# V4-AddOnESP8266-V01-001.net
KiCad netlist of a schematic drawn in EAGLE
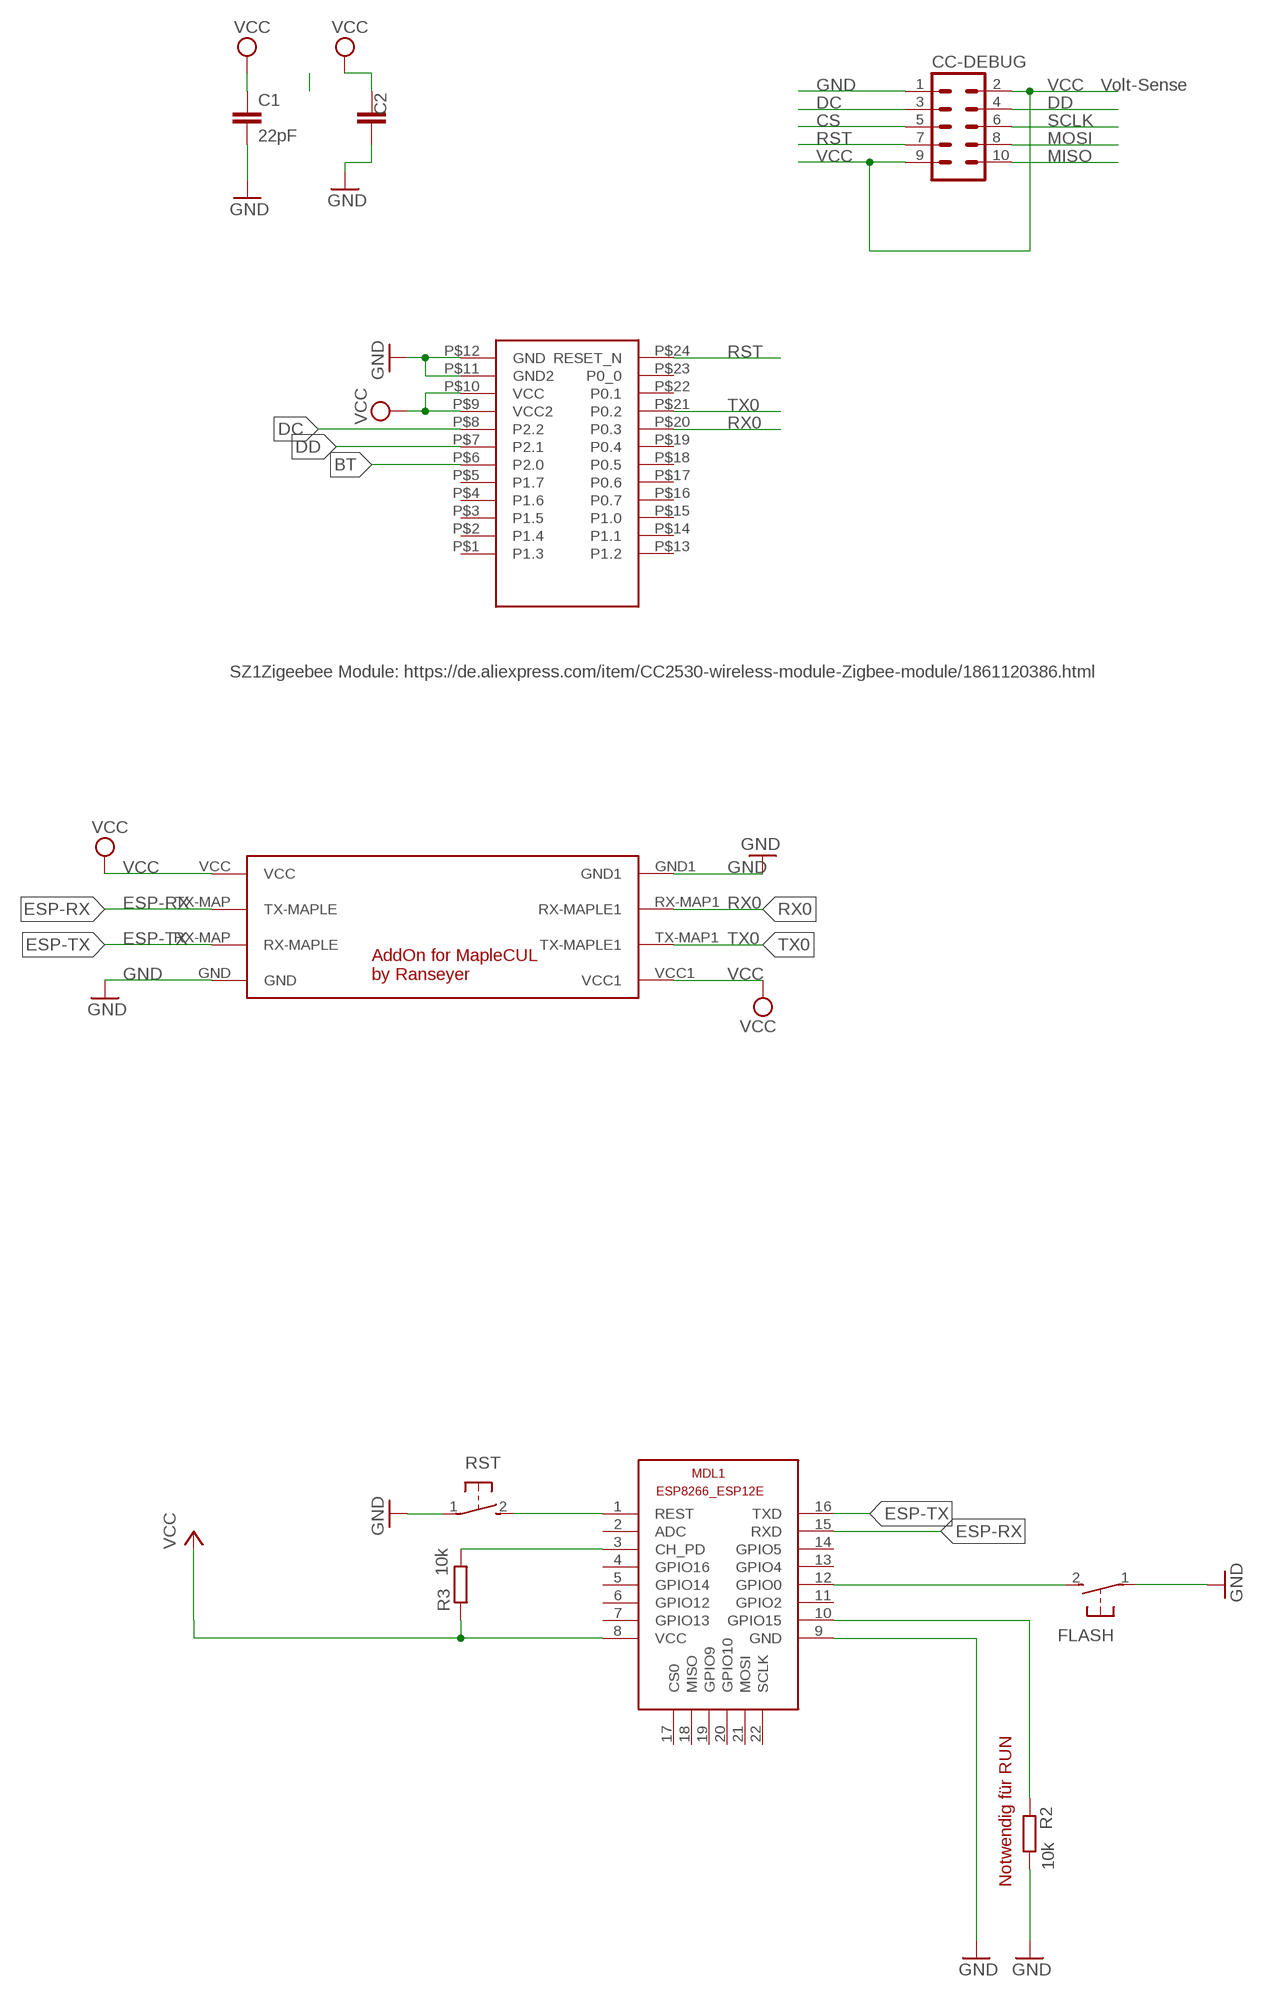
[diagram p0: schematic, sheet 1]

(export (version "E")
  (design (tool "Eeschema 10.0.6"))
  (components
    (comp (ref "C1")
      (value "22pF")
      (footprint "eagle-import:C0805")
      (libsource (lib "eagle-import") (part "C-EUC0805"))
    )
    (comp (ref "C2")
      (value "C-EUC1812")
      (footprint "eagle-import:C1812")
      (libsource (lib "eagle-import") (part "C-EUC1812"))
    )
    (comp (ref "CC-DEBUG")
      (value "CONN_05X2SHD_LOCK")
      (footprint "eagle-import:2X5-SHROUDED_LOCK")
      (libsource (lib "eagle-import") (part "CONN_05X2SHD_LOCK"))
    )
    (comp (ref "FLASH")
      (value "DTSM-3")
      (footprint "eagle-import:DTSM-3")
      (libsource (lib "eagle-import") (part "DTSM-3"))
    )
    (comp (ref "MDL1")
      (value "ESP8266-12EESP8266-ESP12E")
      (footprint "eagle-import:ESP8266-ESP12E")
      (libsource (lib "eagle-import") (part "ESP8266-12EESP8266-ESP12E"))
    )
    (comp (ref "R2")
      (value "10k")
      (footprint "eagle-import:M1206")
      (libsource (lib "eagle-import") (part "R-EU_M1206"))
    )
    (comp (ref "R3")
      (value "10k")
      (footprint "eagle-import:M1206")
      (libsource (lib "eagle-import") (part "R-EU_M1206"))
    )
    (comp (ref "RST")
      (value "DTSM-3")
      (footprint "eagle-import:DTSM-3")
      (libsource (lib "eagle-import") (part "DTSM-3"))
    )
    (comp (ref "U$1")
      (value "MAPLE-CUL-ADDON-V01")
      (footprint "eagle-import:MAPLE-CUL-V01")
      (libsource (lib "eagle-import") (part "MAPLE-CUL-ADDON-V01"))
    )
    (comp (ref "U$2")
      (value "CC2530")
      (footprint "eagle-import:SZ1ZIGBEE-SMD")
      (libsource (lib "eagle-import") (part "CC2530"))
    )
  )
  (nets
    (net (code "1") (name "/CS") (class "Default")
      (node (ref "CC-DEBUG") (pin "5") (pinfunction "5_5") (pintype "passive"))
    )
    (net (code "2") (name "/MISO") (class "Default")
      (node (ref "CC-DEBUG") (pin "10") (pinfunction "10_10") (pintype "passive"))
    )
    (net (code "3") (name "/MOSI") (class "Default")
      (node (ref "CC-DEBUG") (pin "8") (pinfunction "8_8") (pintype "passive"))
    )
    (net (code "4") (name "/RST") (class "Default")
      (node (ref "CC-DEBUG") (pin "7") (pinfunction "7_7") (pintype "passive"))
      (node (ref "U$2") (pin "P$24") (pinfunction "RESET_N_P$24") (pintype "bidirectional"))
    )
    (net (code "5") (name "/SCLK") (class "Default")
      (node (ref "CC-DEBUG") (pin "6") (pinfunction "6_6") (pintype "passive"))
    )
    (net (code "6") (name "BT") (class "Default")
      (node (ref "U$2") (pin "P$6") (pinfunction "P2.0_P$6") (pintype "bidirectional"))
    )
    (net (code "7") (name "DC") (class "Default")
      (node (ref "CC-DEBUG") (pin "3") (pinfunction "3_3") (pintype "passive"))
      (node (ref "U$2") (pin "P$8") (pinfunction "P2.2_P$8") (pintype "bidirectional"))
    )
    (net (code "8") (name "DD") (class "Default")
      (node (ref "CC-DEBUG") (pin "4") (pinfunction "4_4") (pintype "passive"))
      (node (ref "U$2") (pin "P$7") (pinfunction "P2.1_P$7") (pintype "bidirectional"))
    )
    (net (code "9") (name "ESP-RX") (class "Default")
      (node (ref "MDL1") (pin "15") (pinfunction "RXD_15") (pintype "bidirectional"))
      (node (ref "U$1") (pin "TX-MAP") (pinfunction "TX-MAPLE_TX-MAP") (pintype "bidirectional"))
    )
    (net (code "10") (name "ESP-TX") (class "Default")
      (node (ref "MDL1") (pin "16") (pinfunction "TXD_16") (pintype "bidirectional"))
      (node (ref "U$1") (pin "RX-MAP") (pinfunction "RX-MAPLE_RX-MAP") (pintype "bidirectional"))
    )
    (net (code "11") (name "GND") (class "Default")
      (node (ref "C1") (pin "2") (pinfunction "2_2") (pintype "passive"))
      (node (ref "C2") (pin "1") (pinfunction "1_1") (pintype "passive"))
      (node (ref "CC-DEBUG") (pin "1") (pinfunction "1_1") (pintype "passive"))
      (node (ref "FLASH") (pin "1") (pinfunction "1_1") (pintype "passive"))
      (node (ref "MDL1") (pin "9") (pinfunction "GND_9") (pintype "bidirectional"))
      (node (ref "R2") (pin "2") (pinfunction "2_2") (pintype "passive"))
      (node (ref "RST") (pin "1") (pinfunction "1_1") (pintype "passive"))
      (node (ref "U$1") (pin "GND") (pinfunction "GND_GND") (pintype "bidirectional"))
      (node (ref "U$1") (pin "GND1") (pinfunction "GND1_GND1") (pintype "bidirectional"))
      (node (ref "U$2") (pin "P$11") (pinfunction "GND2_P$11") (pintype "bidirectional"))
      (node (ref "U$2") (pin "P$12") (pinfunction "GND_P$12") (pintype "bidirectional"))
    )
    (net (code "12") (name "Net-(MDL1-CH_PD)") (class "Default")
      (node (ref "MDL1") (pin "3") (pinfunction "CH_PD_3") (pintype "bidirectional"))
      (node (ref "R3") (pin "2") (pinfunction "2_2") (pintype "passive"))
    )
    (net (code "13") (name "Net-(MDL1-GPIO0)") (class "Default")
      (node (ref "FLASH") (pin "2") (pinfunction "2_2") (pintype "passive"))
      (node (ref "MDL1") (pin "12") (pinfunction "GPIO0_12") (pintype "bidirectional"))
    )
    (net (code "14") (name "Net-(MDL1-GPIO15)") (class "Default")
      (node (ref "MDL1") (pin "10") (pinfunction "GPIO15_10") (pintype "bidirectional"))
      (node (ref "R2") (pin "1") (pinfunction "1_1") (pintype "passive"))
    )
    (net (code "15") (name "Net-(MDL1-REST)") (class "Default")
      (node (ref "MDL1") (pin "1") (pinfunction "REST_1") (pintype "bidirectional"))
      (node (ref "RST") (pin "2") (pinfunction "2_2") (pintype "passive"))
    )
    (net (code "16") (name "RX0") (class "Default")
      (node (ref "U$1") (pin "RX-MAP1") (pinfunction "RX-MAPLE1_RX-MAP1") (pintype "bidirectional"))
      (node (ref "U$2") (pin "P$20") (pinfunction "P0.3_P$20") (pintype "bidirectional"))
    )
    (net (code "17") (name "TX0") (class "Default")
      (node (ref "U$1") (pin "TX-MAP1") (pinfunction "TX-MAPLE1_TX-MAP1") (pintype "bidirectional"))
      (node (ref "U$2") (pin "P$21") (pinfunction "P0.2_P$21") (pintype "bidirectional"))
    )
    (net (code "18") (name "VCC") (class "Default")
      (node (ref "C1") (pin "1") (pinfunction "1_1") (pintype "passive"))
      (node (ref "C2") (pin "2") (pinfunction "2_2") (pintype "passive"))
      (node (ref "CC-DEBUG") (pin "2") (pinfunction "2_2") (pintype "passive"))
      (node (ref "CC-DEBUG") (pin "9") (pinfunction "9_9") (pintype "passive"))
      (node (ref "MDL1") (pin "8") (pinfunction "VCC_8") (pintype "bidirectional"))
      (node (ref "R3") (pin "1") (pinfunction "1_1") (pintype "passive"))
      (node (ref "U$1") (pin "VCC") (pinfunction "VCC_VCC") (pintype "bidirectional"))
      (node (ref "U$1") (pin "VCC1") (pinfunction "VCC1_VCC1") (pintype "bidirectional"))
      (node (ref "U$2") (pin "P$10") (pinfunction "VCC_P$10") (pintype "bidirectional"))
      (node (ref "U$2") (pin "P$9") (pinfunction "VCC2_P$9") (pintype "bidirectional"))
    )
    (net (code "19") (name "unconnected-(MDL1-ADC-Pad2)") (class "Default")
      (node (ref "MDL1") (pin "2") (pinfunction "ADC_2") (pintype "bidirectional"))
    )
    (net (code "20") (name "unconnected-(MDL1-CS0-Pad17)") (class "Default")
      (node (ref "MDL1") (pin "17") (pinfunction "CS0_17") (pintype "bidirectional"))
    )
    (net (code "21") (name "unconnected-(MDL1-GPIO2-Pad11)") (class "Default")
      (node (ref "MDL1") (pin "11") (pinfunction "GPIO2_11") (pintype "bidirectional"))
    )
    (net (code "22") (name "unconnected-(MDL1-GPIO4-Pad13)") (class "Default")
      (node (ref "MDL1") (pin "13") (pinfunction "GPIO4_13") (pintype "bidirectional"))
    )
    (net (code "23") (name "unconnected-(MDL1-GPIO5-Pad14)") (class "Default")
      (node (ref "MDL1") (pin "14") (pinfunction "GPIO5_14") (pintype "bidirectional"))
    )
    (net (code "24") (name "unconnected-(MDL1-GPIO9-Pad19)") (class "Default")
      (node (ref "MDL1") (pin "19") (pinfunction "GPIO9_19") (pintype "bidirectional"))
    )
    (net (code "25") (name "unconnected-(MDL1-GPIO10-Pad20)") (class "Default")
      (node (ref "MDL1") (pin "20") (pinfunction "GPIO10_20") (pintype "bidirectional"))
    )
    (net (code "26") (name "unconnected-(MDL1-GPIO12-Pad6)") (class "Default")
      (node (ref "MDL1") (pin "6") (pinfunction "GPIO12_6") (pintype "bidirectional"))
    )
    (net (code "27") (name "unconnected-(MDL1-GPIO13-Pad7)") (class "Default")
      (node (ref "MDL1") (pin "7") (pinfunction "GPIO13_7") (pintype "bidirectional"))
    )
    (net (code "28") (name "unconnected-(MDL1-GPIO14-Pad5)") (class "Default")
      (node (ref "MDL1") (pin "5") (pinfunction "GPIO14_5") (pintype "bidirectional"))
    )
    (net (code "29") (name "unconnected-(MDL1-GPIO16-Pad4)") (class "Default")
      (node (ref "MDL1") (pin "4") (pinfunction "GPIO16_4") (pintype "bidirectional"))
    )
    (net (code "30") (name "unconnected-(MDL1-MISO-Pad18)") (class "Default")
      (node (ref "MDL1") (pin "18") (pinfunction "MISO_18") (pintype "bidirectional"))
    )
    (net (code "31") (name "unconnected-(MDL1-MOSI-Pad21)") (class "Default")
      (node (ref "MDL1") (pin "21") (pinfunction "MOSI_21") (pintype "bidirectional"))
    )
    (net (code "32") (name "unconnected-(MDL1-SCLK-Pad22)") (class "Default")
      (node (ref "MDL1") (pin "22") (pinfunction "SCLK_22") (pintype "bidirectional"))
    )
    (net (code "33") (name "unconnected-(U$2-P0.1-PadP$22)") (class "Default")
      (node (ref "U$2") (pin "P$22") (pinfunction "P0.1_P$22") (pintype "bidirectional"))
    )
    (net (code "34") (name "unconnected-(U$2-P0.4-PadP$19)") (class "Default")
      (node (ref "U$2") (pin "P$19") (pinfunction "P0.4_P$19") (pintype "bidirectional"))
    )
    (net (code "35") (name "unconnected-(U$2-P0.5-PadP$18)") (class "Default")
      (node (ref "U$2") (pin "P$18") (pinfunction "P0.5_P$18") (pintype "bidirectional"))
    )
    (net (code "36") (name "unconnected-(U$2-P0.6-PadP$17)") (class "Default")
      (node (ref "U$2") (pin "P$17") (pinfunction "P0.6_P$17") (pintype "bidirectional"))
    )
    (net (code "37") (name "unconnected-(U$2-P0.7-PadP$16)") (class "Default")
      (node (ref "U$2") (pin "P$16") (pinfunction "P0.7_P$16") (pintype "bidirectional"))
    )
    (net (code "38") (name "unconnected-(U$2-P0_0-PadP$23)") (class "Default")
      (node (ref "U$2") (pin "P$23") (pinfunction "P0_0_P$23") (pintype "bidirectional"))
    )
    (net (code "39") (name "unconnected-(U$2-P1.0-PadP$15)") (class "Default")
      (node (ref "U$2") (pin "P$15") (pinfunction "P1.0_P$15") (pintype "bidirectional"))
    )
    (net (code "40") (name "unconnected-(U$2-P1.1-PadP$14)") (class "Default")
      (node (ref "U$2") (pin "P$14") (pinfunction "P1.1_P$14") (pintype "bidirectional"))
    )
    (net (code "41") (name "unconnected-(U$2-P1.2-PadP$13)") (class "Default")
      (node (ref "U$2") (pin "P$13") (pinfunction "P1.2_P$13") (pintype "bidirectional"))
    )
    (net (code "42") (name "unconnected-(U$2-P1.3-PadP$1)") (class "Default")
      (node (ref "U$2") (pin "P$1") (pinfunction "P1.3_P$1") (pintype "bidirectional"))
    )
    (net (code "43") (name "unconnected-(U$2-P1.4-PadP$2)") (class "Default")
      (node (ref "U$2") (pin "P$2") (pinfunction "P1.4_P$2") (pintype "bidirectional"))
    )
    (net (code "44") (name "unconnected-(U$2-P1.5-PadP$3)") (class "Default")
      (node (ref "U$2") (pin "P$3") (pinfunction "P1.5_P$3") (pintype "bidirectional"))
    )
    (net (code "45") (name "unconnected-(U$2-P1.6-PadP$4)") (class "Default")
      (node (ref "U$2") (pin "P$4") (pinfunction "P1.6_P$4") (pintype "bidirectional"))
    )
    (net (code "46") (name "unconnected-(U$2-P1.7-PadP$5)") (class "Default")
      (node (ref "U$2") (pin "P$5") (pinfunction "P1.7_P$5") (pintype "bidirectional"))
    )
  )
)
